# Analog_blocks.net
KiCad netlist of a schematic drawn in EAGLE
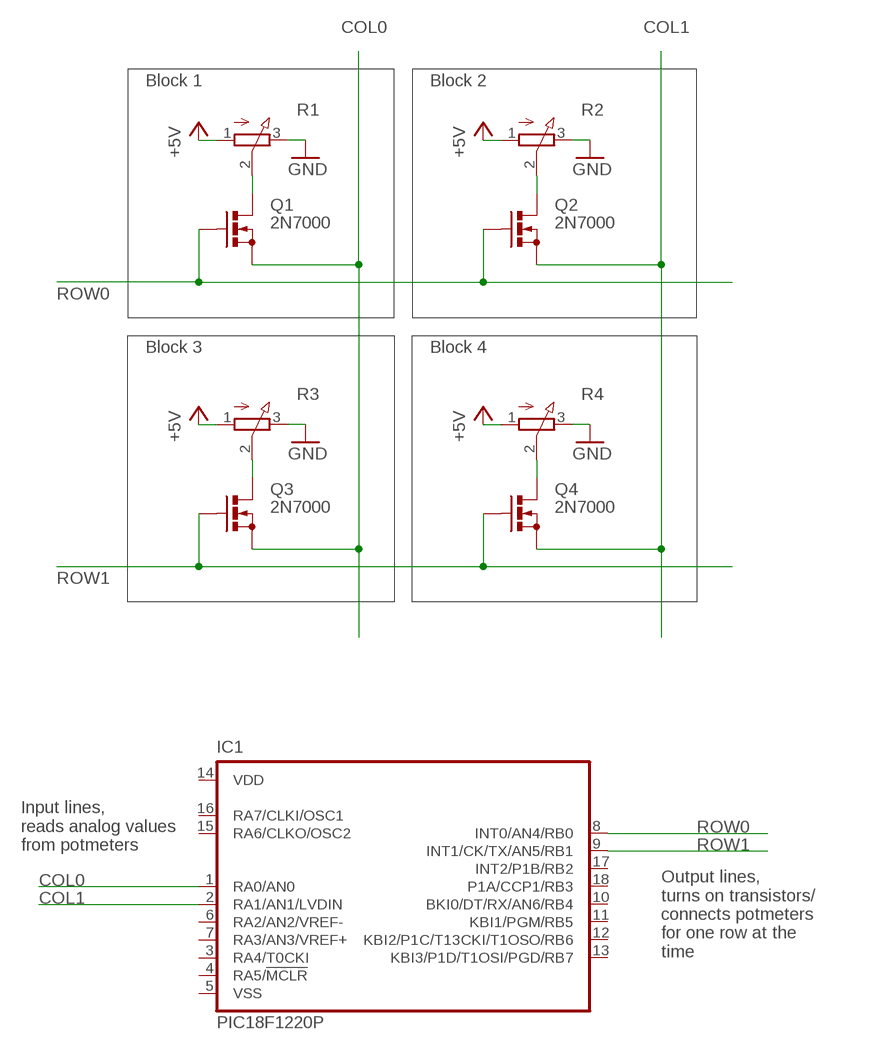
[diagram p0: schematic, sheet 1]

(export (version "E")
  (design (tool "Eeschema 10.0.6"))
  (components
    (comp (ref "IC1")
      (value "PIC18F1220P")
      (footprint "eagle-import:DIL18")
      (fields (field (name "MF") "MICROCHIP") (field (name "MPN") "PIC18F1220-I/P"))
      (libsource (lib "eagle-import") (part "PIC18F120P2"))
    )
    (comp (ref "Q1")
      (value "2N7000")
      (footprint "eagle-import:SOT54E")
      (libsource (lib "eagle-import") (part "2N7000"))
    )
    (comp (ref "Q2")
      (value "2N7000")
      (footprint "eagle-import:SOT54E")
      (libsource (lib "eagle-import") (part "2N7000"))
    )
    (comp (ref "Q3")
      (value "2N7000")
      (footprint "eagle-import:SOT54E")
      (libsource (lib "eagle-import") (part "2N7000"))
    )
    (comp (ref "Q4")
      (value "2N7000")
      (footprint "eagle-import:SOT54E")
      (libsource (lib "eagle-import") (part "2N7000"))
    )
    (comp (ref "R1")
      (value "3RP/1610N")
      (footprint "eagle-import:3RP_1610N")
      (libsource (lib "eagle-import") (part "3RP/1610N"))
    )
    (comp (ref "R2")
      (value "3RP/1610N")
      (footprint "eagle-import:3RP_1610N")
      (libsource (lib "eagle-import") (part "3RP/1610N"))
    )
    (comp (ref "R3")
      (value "3RP/1610N")
      (footprint "eagle-import:3RP_1610N")
      (libsource (lib "eagle-import") (part "3RP/1610N"))
    )
    (comp (ref "R4")
      (value "3RP/1610N")
      (footprint "eagle-import:3RP_1610N")
      (libsource (lib "eagle-import") (part "3RP/1610N"))
    )
  )
  (nets
    (net (code "1") (name "+5V") (class "Default")
      (node (ref "R1") (pin "1") (pinfunction "A_1") (pintype "passive"))
      (node (ref "R2") (pin "1") (pinfunction "A_1") (pintype "passive"))
      (node (ref "R3") (pin "1") (pinfunction "A_1") (pintype "passive"))
      (node (ref "R4") (pin "1") (pinfunction "A_1") (pintype "passive"))
    )
    (net (code "2") (name "/COL0") (class "Default")
      (node (ref "IC1") (pin "1") (pinfunction "RA0/AN0_1") (pintype "bidirectional"))
      (node (ref "Q1") (pin "D") (pinfunction "S_D") (pintype "passive"))
      (node (ref "Q3") (pin "D") (pinfunction "S_D") (pintype "passive"))
    )
    (net (code "3") (name "/COL1") (class "Default")
      (node (ref "IC1") (pin "2") (pinfunction "RA1/AN1/LVDIN_2") (pintype "bidirectional"))
      (node (ref "Q2") (pin "D") (pinfunction "S_D") (pintype "passive"))
      (node (ref "Q4") (pin "D") (pinfunction "S_D") (pintype "passive"))
    )
    (net (code "4") (name "/ROW0") (class "Default")
      (node (ref "IC1") (pin "8") (pinfunction "INT0/AN4/RB0_8") (pintype "bidirectional"))
      (node (ref "Q1") (pin "G") (pinfunction "G_G") (pintype "passive"))
      (node (ref "Q2") (pin "G") (pinfunction "G_G") (pintype "passive"))
    )
    (net (code "5") (name "/ROW1") (class "Default")
      (node (ref "IC1") (pin "9") (pinfunction "INT1/CK/TX/AN5/RB1_9") (pintype "bidirectional"))
      (node (ref "Q3") (pin "G") (pinfunction "G_G") (pintype "passive"))
      (node (ref "Q4") (pin "G") (pinfunction "G_G") (pintype "passive"))
    )
    (net (code "6") (name "/VDD") (class "Default")
      (node (ref "IC1") (pin "14") (pinfunction "VDD_14") (pintype "power_in"))
    )
    (net (code "7") (name "/VSS") (class "Default")
      (node (ref "IC1") (pin "5") (pinfunction "VSS_5") (pintype "power_in"))
    )
    (net (code "8") (name "GND") (class "Default")
      (node (ref "R1") (pin "3") (pinfunction "E_3") (pintype "passive"))
      (node (ref "R2") (pin "3") (pinfunction "E_3") (pintype "passive"))
      (node (ref "R3") (pin "3") (pinfunction "E_3") (pintype "passive"))
      (node (ref "R4") (pin "3") (pinfunction "E_3") (pintype "passive"))
    )
    (net (code "9") (name "Net-(Q1-D)") (class "Default")
      (node (ref "Q1") (pin "S") (pinfunction "D_S") (pintype "passive"))
      (node (ref "R1") (pin "2") (pinfunction "S_2") (pintype "passive"))
    )
    (net (code "10") (name "Net-(Q2-D)") (class "Default")
      (node (ref "Q2") (pin "S") (pinfunction "D_S") (pintype "passive"))
      (node (ref "R2") (pin "2") (pinfunction "S_2") (pintype "passive"))
    )
    (net (code "11") (name "Net-(Q3-D)") (class "Default")
      (node (ref "Q3") (pin "S") (pinfunction "D_S") (pintype "passive"))
      (node (ref "R3") (pin "2") (pinfunction "S_2") (pintype "passive"))
    )
    (net (code "12") (name "Net-(Q4-D)") (class "Default")
      (node (ref "Q4") (pin "S") (pinfunction "D_S") (pintype "passive"))
      (node (ref "R4") (pin "2") (pinfunction "S_2") (pintype "passive"))
    )
    (net (code "13") (name "unconnected-(IC1-BKI0{slash}DT{slash}RX{slash}AN6{slash}RB4-Pad10)") (class "Default")
      (node (ref "IC1") (pin "10") (pinfunction "BKI0/DT/RX/AN6/RB4_10") (pintype "bidirectional"))
    )
    (net (code "14") (name "unconnected-(IC1-INT2{slash}P1B{slash}RB2-Pad17)") (class "Default")
      (node (ref "IC1") (pin "17") (pinfunction "INT2/P1B/RB2_17") (pintype "bidirectional"))
    )
    (net (code "15") (name "unconnected-(IC1-KBI1{slash}PGM{slash}RB5-Pad11)") (class "Default")
      (node (ref "IC1") (pin "11") (pinfunction "KBI1/PGM/RB5_11") (pintype "bidirectional"))
    )
    (net (code "16") (name "unconnected-(IC1-KBI2{slash}P1C{slash}T13CKI{slash}T1OSO{slash}RB6-Pad12)") (class "Default")
      (node (ref "IC1") (pin "12") (pinfunction "KBI2/P1C/T13CKI/T1OSO/RB6_12") (pintype "bidirectional"))
    )
    (net (code "17") (name "unconnected-(IC1-KBI3{slash}P1D{slash}T1OSI{slash}PGD{slash}RB7-Pad13)") (class "Default")
      (node (ref "IC1") (pin "13") (pinfunction "KBI3/P1D/T1OSI/PGD/RB7_13") (pintype "bidirectional"))
    )
    (net (code "18") (name "unconnected-(IC1-P1A{slash}CCP1{slash}RB3-Pad18)") (class "Default")
      (node (ref "IC1") (pin "18") (pinfunction "P1A/CCP1/RB3_18") (pintype "bidirectional"))
    )
    (net (code "19") (name "unconnected-(IC1-RA2{slash}AN2{slash}VREF--Pad6)") (class "Default")
      (node (ref "IC1") (pin "6") (pinfunction "RA2/AN2/VREF-_6") (pintype "bidirectional"))
    )
    (net (code "20") (name "unconnected-(IC1-RA3{slash}AN3{slash}VREF+-Pad7)") (class "Default")
      (node (ref "IC1") (pin "7") (pinfunction "RA3/AN3/VREF+_7") (pintype "bidirectional"))
    )
    (net (code "21") (name "unconnected-(IC1-RA4{slash}T0CKI-Pad3)") (class "Default")
      (node (ref "IC1") (pin "3") (pinfunction "RA4/T0CKI_3") (pintype "bidirectional"))
    )
    (net (code "22") (name "unconnected-(IC1-RA5{slash}~{MCLR}-Pad4)") (class "Default")
      (node (ref "IC1") (pin "4") (pinfunction "RA5/~{MCLR}_4") (pintype "input"))
    )
    (net (code "23") (name "unconnected-(IC1-RA6{slash}CLKO{slash}OSC2-Pad15)") (class "Default")
      (node (ref "IC1") (pin "15") (pinfunction "RA6/CLKO/OSC2_15") (pintype "bidirectional"))
    )
    (net (code "24") (name "unconnected-(IC1-RA7{slash}CLKI{slash}OSC1-Pad16)") (class "Default")
      (node (ref "IC1") (pin "16") (pinfunction "RA7/CLKI/OSC1_16") (pintype "bidirectional"))
    )
  )
)
